# INPUTS.net
KiCad netlist of a schematic drawn in Altium Designer
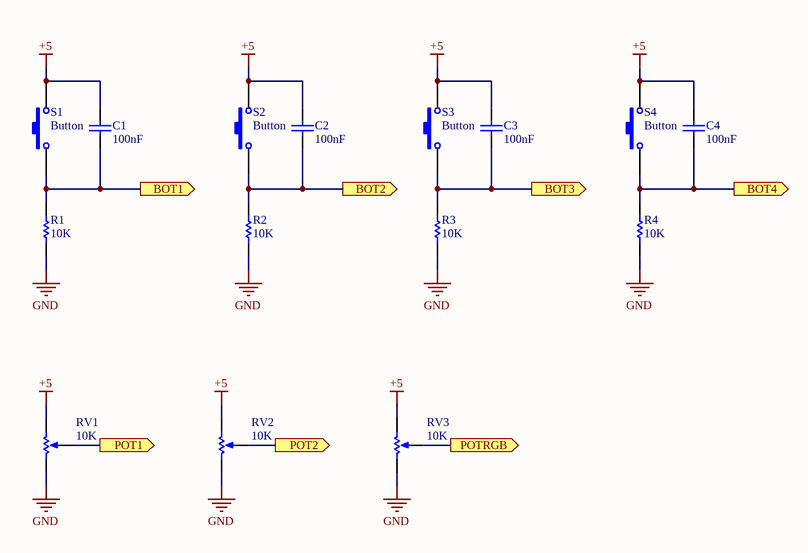
[diagram p0: INPUTS.SchDoc]

(export (version "E")
  (design (tool "Eeschema 10.0.6"))
  (components
    (comp (ref "C1")
      (value "100nF")
      (footprint "SMD Capacitor")
      (description "Multilayer Ceramic\r\nCapacitor 0805")
      (libsource (lib "Aken") (part "SMD Capacitor"))
    )
    (comp (ref "C2")
      (value "100nF")
      (footprint "SMD Capacitor")
      (description "Multilayer Ceramic\r\nCapacitor 0805")
      (libsource (lib "Aken") (part "SMD Capacitor"))
    )
    (comp (ref "C3")
      (value "100nF")
      (footprint "SMD Capacitor")
      (description "Multilayer Ceramic\r\nCapacitor 0805")
      (libsource (lib "Aken") (part "SMD Capacitor"))
    )
    (comp (ref "C4")
      (value "100nF")
      (footprint "SMD Capacitor")
      (description "Multilayer Ceramic\r\nCapacitor 0805")
      (libsource (lib "Aken") (part "SMD Capacitor"))
    )
    (comp (ref "R1")
      (value "10K")
      (footprint "SMD Resistor")
      (description "SMD Resistor  MCU 0805")
      (libsource (lib "Aken") (part "SMD Resistor"))
    )
    (comp (ref "R2")
      (value "10K")
      (footprint "SMD Resistor")
      (description "SMD Resistor  MCU 0805")
      (libsource (lib "Aken") (part "SMD Resistor"))
    )
    (comp (ref "R3")
      (value "10K")
      (footprint "SMD Resistor")
      (description "SMD Resistor  MCU 0805")
      (libsource (lib "Aken") (part "SMD Resistor"))
    )
    (comp (ref "R4")
      (value "10K")
      (footprint "SMD Resistor")
      (description "SMD Resistor  MCU 0805")
      (libsource (lib "Aken") (part "SMD Resistor"))
    )
    (comp (ref "RV1")
      (value "10K")
      (footprint "Trimpot")
      (description "TRIMMER 10K OHM 0.5W TH")
      (fields
        (field (name "MANUFACTURER") "Murata")
        (field (name "MANUFACTURER PART NUMBER") "PV36W103C01B00")
      )
      (libsource (lib "Adono_Library2") (part "Trimpot"))
    )
    (comp (ref "RV2")
      (value "10K")
      (footprint "Trimpot")
      (description "TRIMMER 10K OHM 0.5W TH")
      (fields
        (field (name "MANUFACTURER") "Murata")
        (field (name "MANUFACTURER PART NUMBER") "PV36W103C01B00")
      )
      (libsource (lib "Adono_Library2") (part "Trimpot"))
    )
    (comp (ref "RV3")
      (value "10K")
      (footprint "Trimpot")
      (description "TRIMMER 10K OHM 0.5W TH")
      (fields
        (field (name "MANUFACTURER") "Murata")
        (field (name "MANUFACTURER PART NUMBER") "PV36W103C01B00")
      )
      (libsource (lib "Adono_Library2") (part "Trimpot"))
    )
    (comp (ref "S1")
      (value "Button")
      (footprint "BUTTON")
      (description "Tactil Switch")
      (fields
        (field (name "MANUFACTURER") "Panasonic")
        (field (name "MANUFACTURER PART NUMBER") "EVQ-PAC07K")
      )
      (libsource (lib "Adono_Library2") (part "Button"))
    )
    (comp (ref "S2")
      (value "Button")
      (footprint "BUTTON")
      (description "Tactil Switch")
      (fields
        (field (name "MANUFACTURER") "Panasonic")
        (field (name "MANUFACTURER PART NUMBER") "EVQ-PAC07K")
      )
      (libsource (lib "Adono_Library2") (part "Button"))
    )
    (comp (ref "S3")
      (value "Button")
      (footprint "BUTTON")
      (description "Tactil Switch")
      (fields
        (field (name "MANUFACTURER") "Panasonic")
        (field (name "MANUFACTURER PART NUMBER") "EVQ-PAC07K")
      )
      (libsource (lib "Adono_Library2") (part "Button"))
    )
    (comp (ref "S4")
      (value "Button")
      (footprint "BUTTON")
      (description "Tactil Switch")
      (fields
        (field (name "MANUFACTURER") "Panasonic")
        (field (name "MANUFACTURER PART NUMBER") "EVQ-PAC07K")
      )
      (libsource (lib "Adono_Library2") (part "Button"))
    )
  )
  (nets
    (net (code "1") (name "+5") (class "Default")
      (node (ref "C1") (pin "2") (pinfunction "2_2") (pintype "passive"))
      (node (ref "C2") (pin "2") (pinfunction "2_2") (pintype "passive"))
      (node (ref "C3") (pin "2") (pinfunction "2_2") (pintype "passive"))
      (node (ref "C4") (pin "2") (pinfunction "2_2") (pintype "passive"))
      (node (ref "RV1") (pin "1") (pinfunction "TOP_1") (pintype "passive"))
      (node (ref "RV2") (pin "1") (pinfunction "TOP_1") (pintype "passive"))
      (node (ref "RV3") (pin "1") (pinfunction "TOP_1") (pintype "passive"))
      (node (ref "S1") (pin "2") (pinfunction "2_2") (pintype "passive"))
      (node (ref "S2") (pin "2") (pinfunction "2_2") (pintype "passive"))
      (node (ref "S3") (pin "2") (pinfunction "2_2") (pintype "passive"))
      (node (ref "S4") (pin "2") (pinfunction "2_2") (pintype "passive"))
    )
    (net (code "2") (name "/BOT1") (class "Default")
      (node (ref "C1") (pin "1") (pinfunction "1_1") (pintype "passive"))
      (node (ref "R1") (pin "2") (pinfunction "2_2") (pintype "passive"))
      (node (ref "S1") (pin "1") (pinfunction "1_1") (pintype "passive"))
    )
    (net (code "3") (name "/BOT2") (class "Default")
      (node (ref "C2") (pin "1") (pinfunction "1_1") (pintype "passive"))
      (node (ref "R2") (pin "2") (pinfunction "2_2") (pintype "passive"))
      (node (ref "S2") (pin "1") (pinfunction "1_1") (pintype "passive"))
    )
    (net (code "4") (name "/BOT3") (class "Default")
      (node (ref "C3") (pin "1") (pinfunction "1_1") (pintype "passive"))
      (node (ref "R3") (pin "2") (pinfunction "2_2") (pintype "passive"))
      (node (ref "S3") (pin "1") (pinfunction "1_1") (pintype "passive"))
    )
    (net (code "5") (name "/BOT4") (class "Default")
      (node (ref "C4") (pin "1") (pinfunction "1_1") (pintype "passive"))
      (node (ref "R4") (pin "2") (pinfunction "2_2") (pintype "passive"))
      (node (ref "S4") (pin "1") (pinfunction "1_1") (pintype "passive"))
    )
    (net (code "6") (name "/POT1") (class "Default")
      (node (ref "RV1") (pin "2") (pinfunction "TAP_2") (pintype "passive"))
    )
    (net (code "7") (name "/POT2") (class "Default")
      (node (ref "RV2") (pin "2") (pinfunction "TAP_2") (pintype "passive"))
    )
    (net (code "8") (name "/POTRGB") (class "Default")
      (node (ref "RV3") (pin "2") (pinfunction "TAP_2") (pintype "passive"))
    )
    (net (code "9") (name "GND") (class "Default")
      (node (ref "R1") (pin "1") (pinfunction "1_1") (pintype "passive"))
      (node (ref "R2") (pin "1") (pinfunction "1_1") (pintype "passive"))
      (node (ref "R3") (pin "1") (pinfunction "1_1") (pintype "passive"))
      (node (ref "R4") (pin "1") (pinfunction "1_1") (pintype "passive"))
      (node (ref "RV1") (pin "3") (pinfunction "BOT_3") (pintype "passive"))
      (node (ref "RV2") (pin "3") (pinfunction "BOT_3") (pintype "passive"))
      (node (ref "RV3") (pin "3") (pinfunction "BOT_3") (pintype "passive"))
    )
  )
)
